# femtoduinoUSB.net
KiCad netlist of a schematic drawn in EAGLE
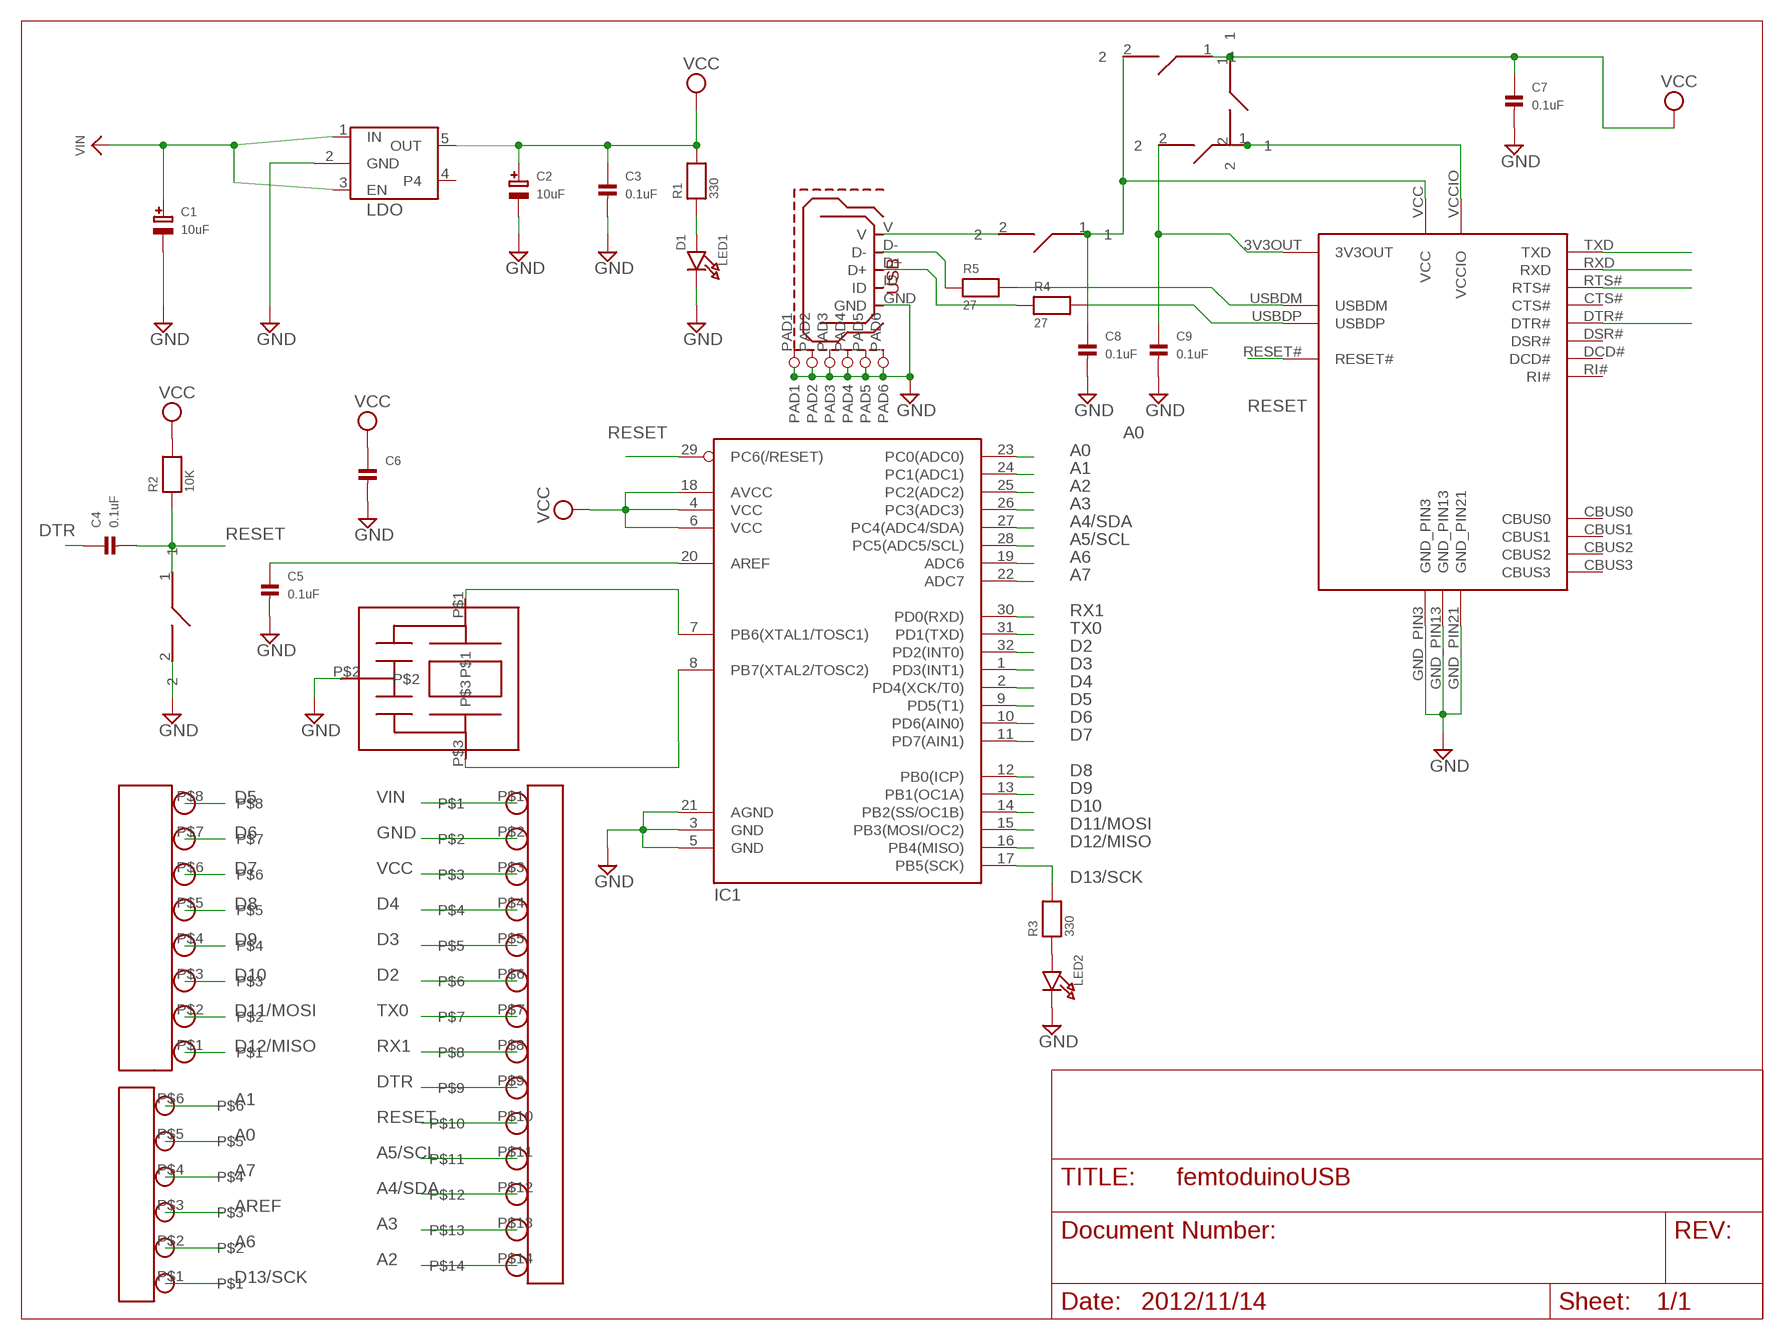
[diagram p0: schematic, sheet 1]

(export (version "E")
  (design (tool "Eeschema 10.0.6"))
  (components
    (comp (ref "C1")
      (value "10uF")
      (footprint "eagle-import:EIA3528-21_B-W")
      (libsource (lib "eagle-import") (part "CAP_TANTALUMB/3528_WAVE"))
    )
    (comp (ref "C2")
      (value "10uF")
      (footprint "eagle-import:EIA3528-21_B-W")
      (libsource (lib "eagle-import") (part "CAP_TANTALUMB/3528_WAVE"))
    )
    (comp (ref "C3")
      (value "0.1uF")
      (footprint "eagle-import:0402")
      (libsource (lib "eagle-import") (part "CAP_CERAMIC0402"))
    )
    (comp (ref "C4")
      (value "0.1uF")
      (footprint "eagle-import:0402")
      (libsource (lib "eagle-import") (part "CAP_CERAMIC0402"))
    )
    (comp (ref "C5")
      (value "0.1uF")
      (footprint "eagle-import:0402")
      (libsource (lib "eagle-import") (part "CAP_CERAMIC0402"))
    )
    (comp (ref "C6")
      (value "CAP_CERAMIC0402")
      (footprint "eagle-import:0402")
      (libsource (lib "eagle-import") (part "CAP_CERAMIC0402"))
    )
    (comp (ref "C7")
      (value "0.1uF")
      (footprint "eagle-import:0402")
      (libsource (lib "eagle-import") (part "CAP_CERAMIC0402"))
    )
    (comp (ref "C8")
      (value "0.1uF")
      (footprint "eagle-import:0402")
      (libsource (lib "eagle-import") (part "CAP_CERAMIC0402"))
    )
    (comp (ref "C9")
      (value "0.1uF")
      (footprint "eagle-import:0402")
      (libsource (lib "eagle-import") (part "CAP_CERAMIC0402"))
    )
    (comp (ref "IC1")
      (value "ATMEGA168MLF")
      (footprint "eagle-import:MLF32")
      (libsource (lib "eagle-import") (part "ATMEGA168MLF"))
    )
    (comp (ref "IC2")
      (value "FT231XQ-R")
      (footprint "eagle-import:FTDI_FT231XQ-R_PACKAGE")
      (libsource (lib "eagle-import") (part "FT231XQ-R"))
    )
    (comp (ref "LED1")
      (value "D1")
      (footprint "eagle-import:CHIPLED_0805")
      (libsource (lib "eagle-import") (part "LED0805"))
    )
    (comp (ref "LED2")
      (value "LED0805")
      (footprint "eagle-import:CHIPLED_0805")
      (libsource (lib "eagle-import") (part "LED0805"))
    )
    (comp (ref "R1")
      (value "330")
      (footprint "eagle-import:0402")
      (libsource (lib "eagle-import") (part "RESISTOR0402"))
    )
    (comp (ref "R2")
      (value "10K")
      (footprint "eagle-import:0402")
      (libsource (lib "eagle-import") (part "RESISTOR0402"))
    )
    (comp (ref "R3")
      (value "330")
      (footprint "eagle-import:0402")
      (libsource (lib "eagle-import") (part "RESISTOR0402"))
    )
    (comp (ref "R4")
      (value "27")
      (footprint "eagle-import:0402")
      (libsource (lib "eagle-import") (part "RESISTOR0402"))
    )
    (comp (ref "R5")
      (value "27")
      (footprint "eagle-import:0402")
      (libsource (lib "eagle-import") (part "RESISTOR0402"))
    )
    (comp (ref "SJ1")
      (value "SPST_SMD")
      (footprint "eagle-import:SPST_SMD")
      (libsource (lib "eagle-import") (part "SPST_SMD"))
    )
    (comp (ref "SJ2")
      (value "SPST_SMD")
      (footprint "eagle-import:SPST_SMD")
      (libsource (lib "eagle-import") (part "SPST_SMD"))
    )
    (comp (ref "SJ3")
      (value "SPST_SMD")
      (footprint "eagle-import:SPST_SMD")
      (libsource (lib "eagle-import") (part "SPST_SMD"))
    )
    (comp (ref "SJ4")
      (value "SPST_SMD")
      (footprint "eagle-import:SPST_SMD")
      (libsource (lib "eagle-import") (part "SPST_SMD"))
    )
    (comp (ref "U$2")
      (value "05_PINHEAD_1X6")
      (footprint "eagle-import:05_PINHEAD_1X6_PACKAGE")
      (libsource (lib "eagle-import") (part "05_PINHEAD_1X6"))
    )
    (comp (ref "U$3")
      (value "05_PINHEAD_1X8")
      (footprint "eagle-import:05_PINHEAD_1X8_PACKAGE")
      (libsource (lib "eagle-import") (part "05_PINHEAD_1X8"))
    )
    (comp (ref "U$4")
      (value "05_PINHEAD_1X14")
      (footprint "eagle-import:05_PINHEAD_1X14_PACKAGE")
      (libsource (lib "eagle-import") (part "05_PINHEAD_1X14"))
    )
    (comp (ref "U$5")
      (value "CSTCE16MOV51-RO")
      (footprint "eagle-import:CSTCE16M0V51-RO_PACKAGE")
      (libsource (lib "eagle-import") (part "CSTCE16MOV51-RO"))
    )
    (comp (ref "U$6")
      (value "SPST_SMD")
      (footprint "eagle-import:SPST_SMD")
      (libsource (lib "eagle-import") (part "SPST_SMD"))
    )
    (comp (ref "U1")
      (value "MIC5205")
      (footprint "eagle-import:LDO_REGULATOR")
      (libsource (lib "eagle-import") (part "LDO_REGULATOR"))
    )
    (comp (ref "USB1")
      (value "USB_MICROB")
      (footprint "eagle-import:USB_MICROB_PACKAGE")
      (libsource (lib "eagle-import") (part "USB_MICROB"))
    )
  )
  (nets
    (net (code "1") (name "/A0") (class "Default")
      (node (ref "IC1") (pin "23") (pinfunction "PC0(ADC0)_23") (pintype "bidirectional"))
      (node (ref "U$2") (pin "P$5") (pinfunction "P$5_P$5") (pintype "bidirectional"))
    )
    (net (code "2") (name "/A1") (class "Default")
      (node (ref "IC1") (pin "24") (pinfunction "PC1(ADC1)_24") (pintype "bidirectional"))
      (node (ref "U$2") (pin "P$6") (pinfunction "P$6_P$6") (pintype "bidirectional"))
    )
    (net (code "3") (name "/A2") (class "Default")
      (node (ref "IC1") (pin "25") (pinfunction "PC2(ADC2)_25") (pintype "bidirectional"))
      (node (ref "U$4") (pin "P$14") (pinfunction "P$14_P$14") (pintype "bidirectional"))
    )
    (net (code "4") (name "/A3") (class "Default")
      (node (ref "IC1") (pin "26") (pinfunction "PC3(ADC3)_26") (pintype "bidirectional"))
      (node (ref "U$4") (pin "P$13") (pinfunction "P$13_P$13") (pintype "bidirectional"))
    )
    (net (code "5") (name "/A4{slash}SDA") (class "Default")
      (node (ref "IC1") (pin "27") (pinfunction "PC4(ADC4/SDA)_27") (pintype "bidirectional"))
      (node (ref "U$4") (pin "P$12") (pinfunction "P$12_P$12") (pintype "bidirectional"))
    )
    (net (code "6") (name "/A5{slash}SCL") (class "Default")
      (node (ref "IC1") (pin "28") (pinfunction "PC5(ADC5/SCL)_28") (pintype "bidirectional"))
      (node (ref "U$4") (pin "P$11") (pinfunction "P$11_P$11") (pintype "bidirectional"))
    )
    (net (code "7") (name "/A6") (class "Default")
      (node (ref "IC1") (pin "19") (pinfunction "ADC6_19") (pintype "bidirectional"))
      (node (ref "U$2") (pin "P$2") (pinfunction "P$2_P$2") (pintype "bidirectional"))
    )
    (net (code "8") (name "/A7") (class "Default")
      (node (ref "IC1") (pin "22") (pinfunction "ADC7_22") (pintype "bidirectional"))
      (node (ref "U$2") (pin "P$4") (pinfunction "P$4_P$4") (pintype "bidirectional"))
    )
    (net (code "9") (name "/AREF") (class "Default")
      (node (ref "C5") (pin "1") (pinfunction "P$1_1") (pintype "passive"))
      (node (ref "IC1") (pin "20") (pinfunction "AREF_20") (pintype "bidirectional"))
      (node (ref "U$2") (pin "P$3") (pinfunction "P$3_P$3") (pintype "bidirectional"))
    )
    (net (code "10") (name "/D2") (class "Default")
      (node (ref "IC1") (pin "32") (pinfunction "PD2(INT0)_32") (pintype "bidirectional"))
      (node (ref "U$4") (pin "P$6") (pinfunction "P$6_P$6") (pintype "bidirectional"))
    )
    (net (code "11") (name "/D3") (class "Default")
      (node (ref "IC1") (pin "1") (pinfunction "PD3(INT1)_1") (pintype "bidirectional"))
      (node (ref "U$4") (pin "P$5") (pinfunction "P$5_P$5") (pintype "bidirectional"))
    )
    (net (code "12") (name "/D4") (class "Default")
      (node (ref "IC1") (pin "2") (pinfunction "PD4(XCK/T0)_2") (pintype "bidirectional"))
      (node (ref "U$4") (pin "P$4") (pinfunction "P$4_P$4") (pintype "bidirectional"))
    )
    (net (code "13") (name "/D5") (class "Default")
      (node (ref "IC1") (pin "9") (pinfunction "PD5(T1)_9") (pintype "bidirectional"))
      (node (ref "U$3") (pin "P$8") (pinfunction "P$8_P$8") (pintype "bidirectional"))
    )
    (net (code "14") (name "/D6") (class "Default")
      (node (ref "IC1") (pin "10") (pinfunction "PD6(AIN0)_10") (pintype "bidirectional"))
      (node (ref "U$3") (pin "P$7") (pinfunction "P$7_P$7") (pintype "bidirectional"))
    )
    (net (code "15") (name "/D7") (class "Default")
      (node (ref "IC1") (pin "11") (pinfunction "PD7(AIN1)_11") (pintype "bidirectional"))
      (node (ref "U$3") (pin "P$6") (pinfunction "P$6_P$6") (pintype "bidirectional"))
    )
    (net (code "16") (name "/D8") (class "Default")
      (node (ref "IC1") (pin "12") (pinfunction "PB0(ICP)_12") (pintype "bidirectional"))
      (node (ref "U$3") (pin "P$5") (pinfunction "P$5_P$5") (pintype "bidirectional"))
    )
    (net (code "17") (name "/D9") (class "Default")
      (node (ref "IC1") (pin "13") (pinfunction "PB1(OC1A)_13") (pintype "bidirectional"))
      (node (ref "U$3") (pin "P$4") (pinfunction "P$4_P$4") (pintype "bidirectional"))
    )
    (net (code "18") (name "/D10") (class "Default")
      (node (ref "IC1") (pin "14") (pinfunction "PB2(SS/OC1B)_14") (pintype "bidirectional"))
      (node (ref "U$3") (pin "P$3") (pinfunction "P$3_P$3") (pintype "bidirectional"))
    )
    (net (code "19") (name "/D11{slash}MOSI") (class "Default")
      (node (ref "IC1") (pin "15") (pinfunction "PB3(MOSI/OC2)_15") (pintype "bidirectional"))
      (node (ref "U$3") (pin "P$2") (pinfunction "P$2_P$2") (pintype "bidirectional"))
    )
    (net (code "20") (name "/D12{slash}MISO") (class "Default")
      (node (ref "IC1") (pin "16") (pinfunction "PB4(MISO)_16") (pintype "bidirectional"))
      (node (ref "U$3") (pin "P$1") (pinfunction "P$1_P$1") (pintype "bidirectional"))
    )
    (net (code "21") (name "/D13{slash}SCK") (class "Default")
      (node (ref "IC1") (pin "17") (pinfunction "PB5(SCK)_17") (pintype "bidirectional"))
      (node (ref "R3") (pin "2") (pinfunction "2_2") (pintype "passive"))
      (node (ref "U$2") (pin "P$1") (pinfunction "P$1_P$1") (pintype "bidirectional"))
    )
    (net (code "22") (name "/DTR") (class "Default")
      (node (ref "C4") (pin "1") (pinfunction "P$1_1") (pintype "passive"))
      (node (ref "U$4") (pin "P$9") (pinfunction "P$9_P$9") (pintype "bidirectional"))
    )
    (net (code "23") (name "/RESET") (class "Default")
      (node (ref "C4") (pin "2") (pinfunction "P$2_2") (pintype "passive"))
      (node (ref "IC1") (pin "29") (pinfunction "PC6(/RESET)_29") (pintype "bidirectional"))
      (node (ref "IC2") (pin "DTR#") (pinfunction "DTR#_DTR#") (pintype "bidirectional"))
      (node (ref "IC2") (pin "RESET#") (pinfunction "RESET#_RESET#") (pintype "bidirectional"))
      (node (ref "R2") (pin "1") (pinfunction "1_1") (pintype "passive"))
      (node (ref "U$4") (pin "P$10") (pinfunction "P$10_P$10") (pintype "bidirectional"))
      (node (ref "U$6") (pin "1") (pinfunction "1_1") (pintype "bidirectional"))
    )
    (net (code "24") (name "/RX1") (class "Default")
      (node (ref "IC1") (pin "30") (pinfunction "PD0(RXD)_30") (pintype "bidirectional"))
      (node (ref "IC2") (pin "TXD") (pinfunction "TXD_TXD") (pintype "bidirectional"))
      (node (ref "U$4") (pin "P$8") (pinfunction "P$8_P$8") (pintype "bidirectional"))
    )
    (net (code "25") (name "/TX0") (class "Default")
      (node (ref "IC1") (pin "31") (pinfunction "PD1(TXD)_31") (pintype "bidirectional"))
      (node (ref "IC2") (pin "RXD") (pinfunction "RXD_RXD") (pintype "bidirectional"))
      (node (ref "U$4") (pin "P$7") (pinfunction "P$7_P$7") (pintype "bidirectional"))
    )
    (net (code "26") (name "GND") (class "Default")
      (node (ref "C1") (pin "-") (pinfunction "-_-") (pintype "passive"))
      (node (ref "C2") (pin "-") (pinfunction "-_-") (pintype "passive"))
      (node (ref "C3") (pin "2") (pinfunction "P$2_2") (pintype "passive"))
      (node (ref "C5") (pin "2") (pinfunction "P$2_2") (pintype "passive"))
      (node (ref "C6") (pin "2") (pinfunction "P$2_2") (pintype "passive"))
      (node (ref "C7") (pin "2") (pinfunction "P$2_2") (pintype "passive"))
      (node (ref "C8") (pin "2") (pinfunction "P$2_2") (pintype "passive"))
      (node (ref "C9") (pin "2") (pinfunction "P$2_2") (pintype "passive"))
      (node (ref "IC1") (pin "21") (pinfunction "AGND_21") (pintype "bidirectional"))
      (node (ref "IC1") (pin "3") (pinfunction "GND_3") (pintype "bidirectional"))
      (node (ref "IC1") (pin "5") (pinfunction "GND_5") (pintype "bidirectional"))
      (node (ref "IC2") (pin "GND_PIN13") (pinfunction "GND_PIN13_GND_PIN13") (pintype "bidirectional"))
      (node (ref "IC2") (pin "GND_PIN21") (pinfunction "GND_PIN21_GND_PIN21") (pintype "bidirectional"))
      (node (ref "IC2") (pin "GND_PIN3") (pinfunction "GND_PIN3_GND_PIN3") (pintype "bidirectional"))
      (node (ref "LED1") (pin "C") (pinfunction "C_C") (pintype "passive"))
      (node (ref "LED2") (pin "C") (pinfunction "C_C") (pintype "passive"))
      (node (ref "U$4") (pin "P$2") (pinfunction "P$2_P$2") (pintype "bidirectional"))
      (node (ref "U$5") (pin "P$2") (pinfunction "P$2_P$2") (pintype "bidirectional"))
      (node (ref "U$6") (pin "2") (pinfunction "2_2") (pintype "bidirectional"))
      (node (ref "U1") (pin "2") (pinfunction "GND_2") (pintype "bidirectional"))
      (node (ref "USB1") (pin "GND") (pinfunction "GND_GND") (pintype "bidirectional"))
    )
    (net (code "27") (name "Net-(C8-P$1)") (class "Default")
      (node (ref "C8") (pin "1") (pinfunction "P$1_1") (pintype "passive"))
      (node (ref "IC2") (pin "VCC") (pinfunction "VCC_VCC") (pintype "bidirectional"))
      (node (ref "SJ1") (pin "1") (pinfunction "1_1") (pintype "bidirectional"))
      (node (ref "SJ2") (pin "2") (pinfunction "2_2") (pintype "bidirectional"))
    )
    (net (code "28") (name "Net-(C9-P$1)") (class "Default")
      (node (ref "C9") (pin "1") (pinfunction "P$1_1") (pintype "passive"))
      (node (ref "IC2") (pin "3V3OUT") (pinfunction "3V3OUT_3V3OUT") (pintype "bidirectional"))
      (node (ref "SJ4") (pin "2") (pinfunction "2_2") (pintype "bidirectional"))
    )
    (net (code "29") (name "Net-(IC1-PB6(XTAL1{slash}TOSC1))") (class "Default")
      (node (ref "IC1") (pin "7") (pinfunction "PB6(XTAL1/TOSC1)_7") (pintype "bidirectional"))
      (node (ref "U$5") (pin "P$1") (pinfunction "P$1_P$1") (pintype "bidirectional"))
    )
    (net (code "30") (name "Net-(IC1-PB7(XTAL2{slash}TOSC2))") (class "Default")
      (node (ref "IC1") (pin "8") (pinfunction "PB7(XTAL2/TOSC2)_8") (pintype "bidirectional"))
      (node (ref "U$5") (pin "P$3") (pinfunction "P$3_P$3") (pintype "bidirectional"))
    )
    (net (code "31") (name "Net-(IC2-PadUSBDM)") (class "Default")
      (node (ref "IC2") (pin "USBDM") (pinfunction "USBDM_USBDM") (pintype "bidirectional"))
      (node (ref "R5") (pin "2") (pinfunction "2_2") (pintype "passive"))
    )
    (net (code "32") (name "Net-(IC2-PadUSBDP)") (class "Default")
      (node (ref "IC2") (pin "USBDP") (pinfunction "USBDP_USBDP") (pintype "bidirectional"))
      (node (ref "R4") (pin "2") (pinfunction "2_2") (pintype "passive"))
    )
    (net (code "33") (name "Net-(IC2-PadVCCIO)") (class "Default")
      (node (ref "IC2") (pin "VCCIO") (pinfunction "VCCIO_VCCIO") (pintype "bidirectional"))
      (node (ref "SJ3") (pin "2") (pinfunction "2_2") (pintype "bidirectional"))
      (node (ref "SJ4") (pin "1") (pinfunction "1_1") (pintype "bidirectional"))
    )
    (net (code "34") (name "Net-(LED1-PadA)") (class "Default")
      (node (ref "LED1") (pin "A") (pinfunction "A_A") (pintype "passive"))
      (node (ref "R1") (pin "1") (pinfunction "1_1") (pintype "passive"))
    )
    (net (code "35") (name "Net-(LED2-PadA)") (class "Default")
      (node (ref "LED2") (pin "A") (pinfunction "A_A") (pintype "passive"))
      (node (ref "R3") (pin "1") (pinfunction "1_1") (pintype "passive"))
    )
    (net (code "36") (name "Net-(R4-Pad1)") (class "Default")
      (node (ref "R4") (pin "1") (pinfunction "1_1") (pintype "passive"))
      (node (ref "USB1") (pin "D+") (pinfunction "D+_D+") (pintype "bidirectional"))
    )
    (net (code "37") (name "Net-(R5-Pad1)") (class "Default")
      (node (ref "R5") (pin "1") (pinfunction "1_1") (pintype "passive"))
      (node (ref "USB1") (pin "D-") (pinfunction "D-_D-") (pintype "bidirectional"))
    )
    (net (code "38") (name "VCC") (class "Default")
      (node (ref "C2") (pin "+") (pinfunction "+_+") (pintype "passive"))
      (node (ref "C3") (pin "1") (pinfunction "P$1_1") (pintype "passive"))
      (node (ref "C6") (pin "1") (pinfunction "P$1_1") (pintype "passive"))
      (node (ref "C7") (pin "1") (pinfunction "P$1_1") (pintype "passive"))
      (node (ref "IC1") (pin "18") (pinfunction "AVCC_18") (pintype "bidirectional"))
      (node (ref "IC1") (pin "4") (pinfunction "VCC_4") (pintype "bidirectional"))
      (node (ref "IC1") (pin "6") (pinfunction "VCC_6") (pintype "bidirectional"))
      (node (ref "R1") (pin "2") (pinfunction "2_2") (pintype "passive"))
      (node (ref "R2") (pin "2") (pinfunction "2_2") (pintype "passive"))
      (node (ref "SJ1") (pin "2") (pinfunction "2_2") (pintype "bidirectional"))
      (node (ref "SJ2") (pin "1") (pinfunction "1_1") (pintype "bidirectional"))
      (node (ref "SJ3") (pin "1") (pinfunction "1_1") (pintype "bidirectional"))
      (node (ref "U$4") (pin "P$3") (pinfunction "P$3_P$3") (pintype "bidirectional"))
      (node (ref "U1") (pin "5") (pinfunction "OUT_5") (pintype "bidirectional"))
      (node (ref "USB1") (pin "V") (pinfunction "V_V") (pintype "bidirectional"))
    )
    (net (code "39") (name "VIN") (class "Default")
      (node (ref "C1") (pin "+") (pinfunction "+_+") (pintype "passive"))
      (node (ref "U$4") (pin "P$1") (pinfunction "P$1_P$1") (pintype "bidirectional"))
      (node (ref "U1") (pin "1") (pinfunction "IN_1") (pintype "bidirectional"))
      (node (ref "U1") (pin "3") (pinfunction "EN_3") (pintype "bidirectional"))
    )
    (net (code "40") (name "unconnected-(IC2-PadCBUS0)") (class "Default")
      (node (ref "IC2") (pin "CBUS0") (pinfunction "CBUS0_CBUS0") (pintype "bidirectional"))
    )
    (net (code "41") (name "unconnected-(IC2-PadCBUS1)") (class "Default")
      (node (ref "IC2") (pin "CBUS1") (pinfunction "CBUS1_CBUS1") (pintype "bidirectional"))
    )
    (net (code "42") (name "unconnected-(IC2-PadCBUS2)") (class "Default")
      (node (ref "IC2") (pin "CBUS2") (pinfunction "CBUS2_CBUS2") (pintype "bidirectional"))
    )
    (net (code "43") (name "unconnected-(IC2-PadCBUS3)") (class "Default")
      (node (ref "IC2") (pin "CBUS3") (pinfunction "CBUS3_CBUS3") (pintype "bidirectional"))
    )
    (net (code "44") (name "unconnected-(IC2-PadCTS#)") (class "Default")
      (node (ref "IC2") (pin "CTS#") (pinfunction "CTS#_CTS#") (pintype "bidirectional"))
    )
    (net (code "45") (name "unconnected-(IC2-PadDCD#)") (class "Default")
      (node (ref "IC2") (pin "DCD#") (pinfunction "DCD#_DCD#") (pintype "bidirectional"))
    )
    (net (code "46") (name "unconnected-(IC2-PadDSR#)") (class "Default")
      (node (ref "IC2") (pin "DSR#") (pinfunction "DSR#_DSR#") (pintype "bidirectional"))
    )
    (net (code "47") (name "unconnected-(IC2-PadRI#)") (class "Default")
      (node (ref "IC2") (pin "RI#") (pinfunction "RI#_RI#") (pintype "bidirectional"))
    )
    (net (code "48") (name "unconnected-(IC2-PadRTS#)") (class "Default")
      (node (ref "IC2") (pin "RTS#") (pinfunction "RTS#_RTS#") (pintype "bidirectional"))
    )
    (net (code "49") (name "unconnected-(U1-P4-Pad4)") (class "Default")
      (node (ref "U1") (pin "4") (pinfunction "P4_4") (pintype "bidirectional"))
    )
    (net (code "50") (name "unconnected-(USB1-PadID)") (class "Default")
      (node (ref "USB1") (pin "ID") (pinfunction "ID_ID") (pintype "bidirectional"))
    )
    (net (code "51") (name "unconnected-(USB1-PadPAD1)") (class "Default")
      (node (ref "USB1") (pin "PAD1") (pinfunction "PAD1_PAD1") (pintype "bidirectional"))
    )
    (net (code "52") (name "unconnected-(USB1-PadPAD2)") (class "Default")
      (node (ref "USB1") (pin "PAD2") (pinfunction "PAD2_PAD2") (pintype "bidirectional"))
    )
    (net (code "53") (name "unconnected-(USB1-PadPAD3)") (class "Default")
      (node (ref "USB1") (pin "PAD3") (pinfunction "PAD3_PAD3") (pintype "bidirectional"))
    )
    (net (code "54") (name "unconnected-(USB1-PadPAD4)") (class "Default")
      (node (ref "USB1") (pin "PAD4") (pinfunction "PAD4_PAD4") (pintype "bidirectional"))
    )
    (net (code "55") (name "unconnected-(USB1-PadPAD5)") (class "Default")
      (node (ref "USB1") (pin "PAD5") (pinfunction "PAD5_PAD5") (pintype "bidirectional"))
    )
    (net (code "56") (name "unconnected-(USB1-PadPAD6)") (class "Default")
      (node (ref "USB1") (pin "PAD6") (pinfunction "PAD6_PAD6") (pintype "bidirectional"))
    )
  )
)
